# Key_Pull-up.net
KiCad netlist of a schematic drawn in Altium Designer
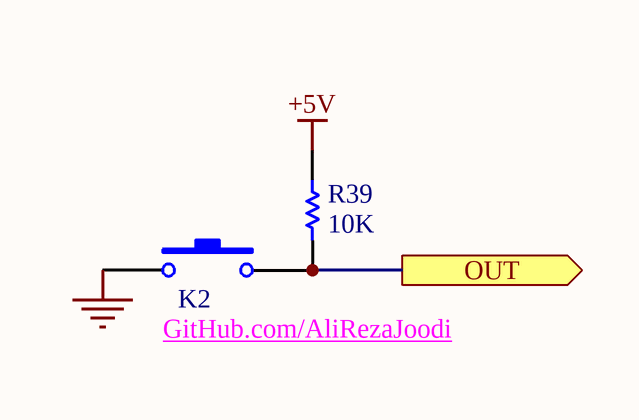
[diagram p0: Key_Pull-up.SchDoc]

(export (version "E")
  (design (tool "Eeschema 10.0.6"))
  (components
    (comp (ref "K2")
      (value "K2")
      (footprint "SPST-2_2")
      (description "Switch")
      (fields (field (name "MANUFACTURER") "Generic Components") (field (name "PUBLISHER") "Altium Limited"))
      (libsource (lib "Miscellaneous Devices") (part "SW-PB"))
    )
    (comp (ref "R39")
      (value "R39")
      (footprint "AXIAL-0.4")
      (description "Resistor")
      (fields
        (field (name "MANUFACTURER") "Generic Components")
        (field (name "ALTIUM_VALUE") "10K")
        (field (name "PUBLISHER") "Altium Limited")
      )
      (libsource (lib "Miscellaneous Devices") (part "Res1"))
    )
  )
  (nets
    (net (code "1") (name "+5V") (class "Default")
      (node (ref "R39") (pin "1") (pinfunction "1_1") (pintype "passive"))
    )
    (net (code "2") (name "/OUT") (class "Default")
      (node (ref "K2") (pin "2") (pinfunction "2_2") (pintype "passive"))
      (node (ref "R39") (pin "2") (pinfunction "2_2") (pintype "passive"))
    )
    (net (code "3") (name "GND") (class "Default")
      (node (ref "K2") (pin "1") (pinfunction "1_1") (pintype "passive"))
    )
  )
)
